# etna-sch-sensor.net
KiCad netlist of a schematic drawn in Altium Designer
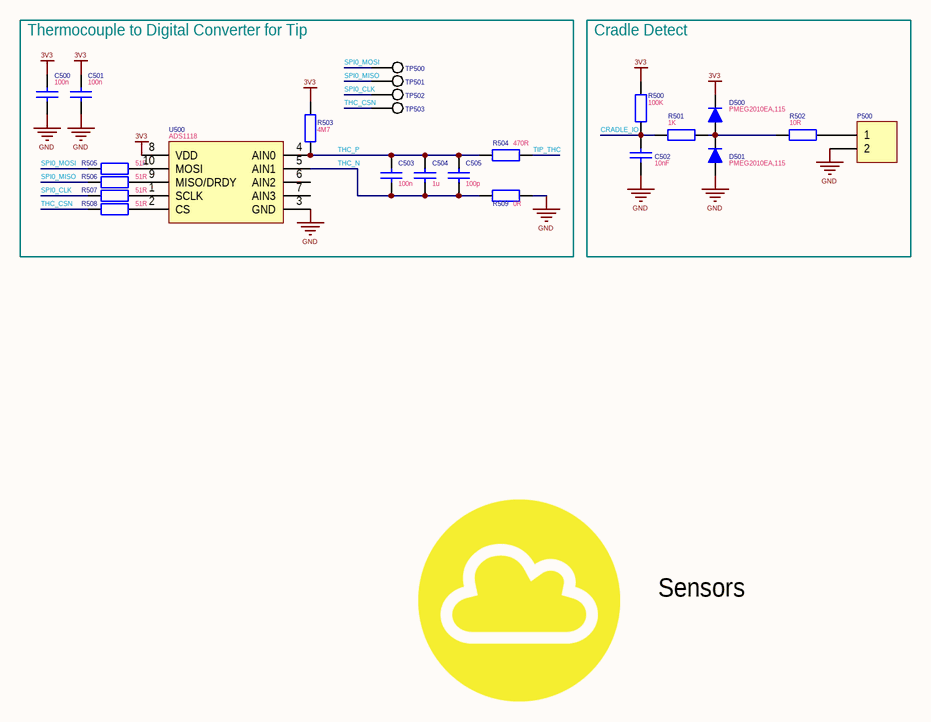
[diagram p0: etna-sch-sensor.SchDoc]

(export (version "E")
  (design (tool "Eeschema 10.0.6"))
  (components
    (comp (ref "C500")
      (value "100n")
      (footprint "0402-capacitor")
      (description "Capacitor")
      (libsource (lib "illysky-components") (part "CAP"))
    )
    (comp (ref "C501")
      (value "100n")
      (footprint "0402-capacitor")
      (description "Capacitor")
      (libsource (lib "illysky-components") (part "CAP"))
    )
    (comp (ref "C502")
      (value "10nF")
      (footprint "0402-capacitor")
      (description "Capacitor")
      (libsource (lib "illysky-components") (part "CAP"))
    )
    (comp (ref "C503")
      (value "100n")
      (footprint "0402-capacitor")
      (description "Capacitor")
      (libsource (lib "illysky-components") (part "CAP"))
    )
    (comp (ref "C504")
      (value "1u")
      (footprint "0402-capacitor")
      (description "Capacitor")
      (libsource (lib "illysky-components") (part "CAP"))
    )
    (comp (ref "C505")
      (value "100p")
      (footprint "0402-capacitor")
      (description "Capacitor")
      (libsource (lib "illysky-components") (part "CAP"))
    )
    (comp (ref "D500")
      (value "PMEG2010EA,115")
      (footprint "SOD-323")
      (description "Diode")
      (fields (field (name "PUBLISHER") "Altium Limited"))
      (libsource (lib "illysky-components") (part "DIODE"))
    )
    (comp (ref "D501")
      (value "PMEG2010EA,115")
      (footprint "SOD-323")
      (description "Diode")
      (fields (field (name "PUBLISHER") "Altium Limited"))
      (libsource (lib "illysky-components") (part "DIODE"))
    )
    (comp (ref "P500")
      (value "~")
      (footprint "HDR1X2")
      (description "Header, 2-Pin")
      (fields (field (name "PUBLISHER") "Altium Limited"))
      (libsource (lib "Miscellaneous Connectors") (part "Header 2"))
    )
    (comp (ref "R500")
      (value "100K")
      (footprint "0402-resistor")
      (description "Resistor")
      (libsource (lib "altium-import") (part "root_3_mirrored_RES_"))
    )
    (comp (ref "R501")
      (value "1K")
      (footprint "0402-resistor")
      (description "Resistor")
      (libsource (lib "altium-import") (part "root_2_mirrored_RES_"))
    )
    (comp (ref "R502")
      (value "10R")
      (footprint "0402-resistor")
      (description "Resistor")
      (libsource (lib "altium-import") (part "root_2_mirrored_RES_"))
    )
    (comp (ref "R503")
      (value "4M7")
      (footprint "0402-resistor")
      (description "Resistor")
      (libsource (lib "altium-import") (part "root_3_mirrored_RES_"))
    )
    (comp (ref "R504")
      (value "470R")
      (footprint "0402-resistor")
      (description "Resistor")
      (libsource (lib "altium-import") (part "root_0_mirrored_RES_"))
    )
    (comp (ref "R505")
      (value "51R")
      (footprint "0402-resistor")
      (description "Resistor")
      (libsource (lib "altium-import") (part "root_0_mirrored_RES_"))
    )
    (comp (ref "R506")
      (value "51R")
      (footprint "0402-resistor")
      (description "Resistor")
      (libsource (lib "altium-import") (part "root_0_mirrored_RES_"))
    )
    (comp (ref "R507")
      (value "51R")
      (footprint "0402-resistor")
      (description "Resistor")
      (libsource (lib "altium-import") (part "root_0_mirrored_RES_"))
    )
    (comp (ref "R508")
      (value "51R")
      (footprint "0402-resistor")
      (description "Resistor")
      (libsource (lib "altium-import") (part "root_0_mirrored_RES_"))
    )
    (comp (ref "R509")
      (value "0R")
      (footprint "0402-resistor")
      (description "Resistor")
      (libsource (lib "altium-import") (part "root_0_mirrored_RES_"))
    )
    (comp (ref "TP500")
      (value "TP")
      (footprint "TESTPOINT")
      (libsource (lib "illysky-components") (part "TEST_POINT"))
    )
    (comp (ref "TP501")
      (value "TP")
      (footprint "TESTPOINT")
      (libsource (lib "illysky-components") (part "TEST_POINT"))
    )
    (comp (ref "TP502")
      (value "TP")
      (footprint "TESTPOINT")
      (libsource (lib "illysky-components") (part "TEST_POINT"))
    )
    (comp (ref "TP503")
      (value "TP")
      (footprint "TESTPOINT")
      (libsource (lib "illysky-components") (part "TEST_POINT"))
    )
    (comp (ref "U500")
      (value "ADS1118")
      (footprint "VSSOP-10")
      (libsource (lib "illysky-components") (part "ADS1118"))
    )
  )
  (nets
    (net (code "1") (name "/CRADLE_IO") (class "Default")
      (node (ref "C502") (pin "2") (pinfunction "2_2") (pintype "passive"))
      (node (ref "R500") (pin "2") (pinfunction "2_2") (pintype "passive"))
      (node (ref "R501") (pin "1") (pinfunction "1_1") (pintype "passive"))
    )
    (net (code "2") (name "/SPI0_CLK") (class "Default")
      (node (ref "R507") (pin "2") (pinfunction "2_2") (pintype "passive"))
      (node (ref "TP502") (pin "1") (pinfunction "GND_1") (pintype "passive"))
    )
    (net (code "3") (name "/SPI0_MISO") (class "Default")
      (node (ref "R506") (pin "2") (pinfunction "2_2") (pintype "passive"))
      (node (ref "TP501") (pin "1") (pinfunction "GND_1") (pintype "passive"))
    )
    (net (code "4") (name "/SPI0_MOSI") (class "Default")
      (node (ref "R505") (pin "2") (pinfunction "2_2") (pintype "passive"))
      (node (ref "TP500") (pin "1") (pinfunction "GND_1") (pintype "passive"))
    )
    (net (code "5") (name "/THC_CSN") (class "Default")
      (node (ref "R508") (pin "2") (pinfunction "2_2") (pintype "passive"))
      (node (ref "TP503") (pin "1") (pinfunction "GND_1") (pintype "passive"))
    )
    (net (code "6") (name "/THC_N") (class "Default")
      (node (ref "C503") (pin "1") (pinfunction "1_1") (pintype "passive"))
      (node (ref "C504") (pin "1") (pinfunction "1_1") (pintype "passive"))
      (node (ref "C505") (pin "1") (pinfunction "1_1") (pintype "passive"))
      (node (ref "R509") (pin "2") (pinfunction "2_2") (pintype "passive"))
      (node (ref "U500") (pin "5") (pinfunction "AIN1_5") (pintype "passive"))
    )
    (net (code "7") (name "/THC_P") (class "Default")
      (node (ref "C503") (pin "2") (pinfunction "2_2") (pintype "passive"))
      (node (ref "C504") (pin "2") (pinfunction "2_2") (pintype "passive"))
      (node (ref "C505") (pin "2") (pinfunction "2_2") (pintype "passive"))
      (node (ref "R503") (pin "2") (pinfunction "2_2") (pintype "passive"))
      (node (ref "R504") (pin "2") (pinfunction "2_2") (pintype "passive"))
      (node (ref "U500") (pin "4") (pinfunction "AIN0_4") (pintype "passive"))
    )
    (net (code "8") (name "/TIP_THC") (class "Default")
      (node (ref "R504") (pin "1") (pinfunction "1_1") (pintype "passive"))
    )
    (net (code "9") (name "3V3") (class "Default")
      (node (ref "C500") (pin "2") (pinfunction "2_2") (pintype "passive"))
      (node (ref "C501") (pin "2") (pinfunction "2_2") (pintype "passive"))
      (node (ref "D500") (pin "2") (pinfunction "K_2") (pintype "passive"))
      (node (ref "R500") (pin "1") (pinfunction "1_1") (pintype "passive"))
      (node (ref "R503") (pin "1") (pinfunction "1_1") (pintype "passive"))
      (node (ref "U500") (pin "8") (pinfunction "VDD_8") (pintype "passive"))
    )
    (net (code "10") (name "GND") (class "Default")
      (node (ref "C500") (pin "1") (pinfunction "1_1") (pintype "passive"))
      (node (ref "C501") (pin "1") (pinfunction "1_1") (pintype "passive"))
      (node (ref "C502") (pin "1") (pinfunction "1_1") (pintype "passive"))
      (node (ref "D501") (pin "1") (pinfunction "A_1") (pintype "passive"))
      (node (ref "P500") (pin "2") (pinfunction "2_2") (pintype "passive"))
      (node (ref "R509") (pin "1") (pinfunction "1_1") (pintype "passive"))
      (node (ref "U500") (pin "3") (pinfunction "GND_3") (pintype "passive"))
    )
    (net (code "11") (name "Net-(D500-A)") (class "Default")
      (node (ref "D500") (pin "1") (pinfunction "A_1") (pintype "passive"))
      (node (ref "D501") (pin "2") (pinfunction "K_2") (pintype "passive"))
      (node (ref "R501") (pin "2") (pinfunction "2_2") (pintype "passive"))
      (node (ref "R502") (pin "1") (pinfunction "1_1") (pintype "passive"))
    )
    (net (code "12") (name "Net-(P500-Pad1)") (class "Default")
      (node (ref "P500") (pin "1") (pinfunction "1_1") (pintype "passive"))
      (node (ref "R502") (pin "2") (pinfunction "2_2") (pintype "passive"))
    )
    (net (code "13") (name "Net-(U500-CS)") (class "Default")
      (node (ref "R508") (pin "1") (pinfunction "1_1") (pintype "passive"))
      (node (ref "U500") (pin "2") (pinfunction "CS_2") (pintype "passive"))
    )
    (net (code "14") (name "Net-(U500-MISO{slash}DRDY)") (class "Default")
      (node (ref "R506") (pin "1") (pinfunction "1_1") (pintype "passive"))
      (node (ref "U500") (pin "9") (pinfunction "MISO/DRDY_9") (pintype "passive"))
    )
    (net (code "15") (name "Net-(U500-MOSI)") (class "Default")
      (node (ref "R505") (pin "1") (pinfunction "1_1") (pintype "passive"))
      (node (ref "U500") (pin "10") (pinfunction "MOSI_10") (pintype "passive"))
    )
    (net (code "16") (name "Net-(U500-SCLK)") (class "Default")
      (node (ref "R507") (pin "1") (pinfunction "1_1") (pintype "passive"))
      (node (ref "U500") (pin "1") (pinfunction "SCLK_1") (pintype "passive"))
    )
    (net (code "17") (name "unconnected-(U500-AIN2-Pad6)") (class "Default")
      (node (ref "U500") (pin "6") (pinfunction "AIN2_6") (pintype "passive"))
    )
    (net (code "18") (name "unconnected-(U500-AIN3-Pad7)") (class "Default")
      (node (ref "U500") (pin "7") (pinfunction "AIN3_7") (pintype "passive"))
    )
  )
)
